# PWR_N3V0.net
KiCad netlist of a schematic drawn in Altium Designer
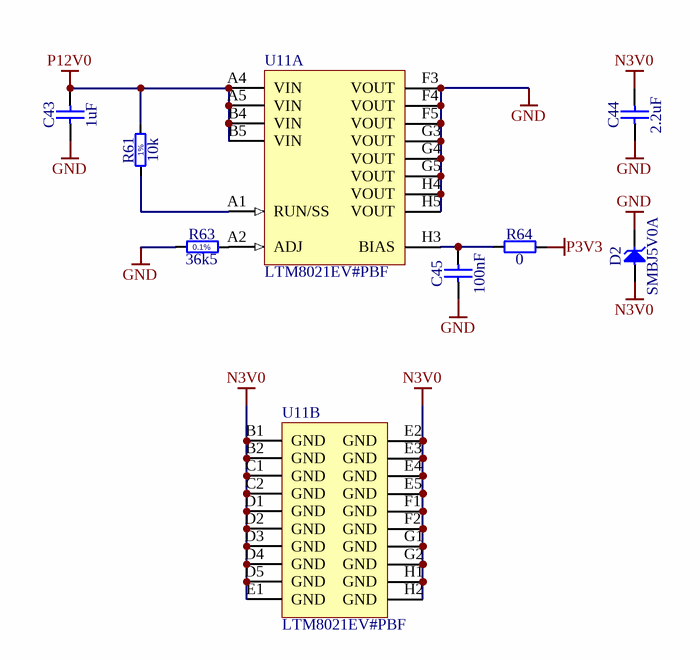
[diagram p0: PWR_N3V0.SchDoc]

(export (version "E")
  (design (tool "Eeschema 10.0.6"))
  (components
    (comp (ref "C43")
      (value "1uF")
      (footprint "CAPC1608X87N")
      (description "Non-polarised capacitor")
      (fields
        (field (name "PART NUMBER") "CC0603_1UF_25V_10%_X7R")
        (field (name "VOLTAGE") "25V")
        (field (name "AUTHOR") "CERN DEM JLC")
      )
      (libsource (lib "Capacitors") (part "Capacitor - non polarized"))
    )
    (comp (ref "C44")
      (value "2.2uF")
      (footprint "CAPC1608X87N")
      (description "Non-polarised capacitor")
      (fields
        (field (name "PART NUMBER") "CC0603_2.2UF_16V_10%_X5R")
        (field (name "VOLTAGE") "16V")
        (field (name "AUTHOR") "CERN DEM JLC")
      )
      (libsource (lib "Capacitors") (part "Capacitor - non polarized"))
    )
    (comp (ref "C45")
      (value "100nF")
      (footprint "CAPC1005X55N")
      (description "Non-polarised capacitor")
      (fields
        (field (name "PART NUMBER") "CC0402_100NF_16V_10%_X5R")
        (field (name "VOLTAGE") "16V")
        (field (name "AUTHOR") "CERN DEM JLC")
      )
      (libsource (lib "Capacitors") (part "Capacitor - non polarized"))
    )
    (comp (ref "D2")
      (value "SMBJ5V0A")
      (footprint "DIOM5336X265N")
      (description "Zener Diode")
      (fields
        (field (name "VOLTAGE") "5V")
        (field (name "POWER") "600W")
        (field (name "AUTHOR") "CERN DEM JLC")
      )
      (libsource (lib "ICs And Semiconductors") (part "Diode Zener"))
    )
    (comp (ref "R61")
      (value "10k")
      (footprint "RESC1005X40N")
      (description "Resistor - 1%")
      (fields
        (field (name "PART NUMBER") "R0402_10K_1%_0.0625W_100PPM")
        (field (name "MANUFACTURER") "GENERIC")
        (field (name "AUTHOR") "CERN DEM JLC")
      )
      (libsource (lib "Resistors") (part "Resistor - 1%"))
    )
    (comp (ref "R63")
      (value "36k5")
      (footprint "RESC1608X55N")
      (description "Resistor - 0.1%")
      (fields
        (field (name "PART NUMBER") "R0603_36K5_0.1%_0.063W_10PPM")
        (field (name "POWER") "0.063W")
        (field (name "AUTHOR") "CERN DEM JLC")
      )
      (libsource (lib "Resistors") (part "Resistor - 0.1%"))
    )
    (comp (ref "R64")
      (value "0")
      (footprint "RESC1005X40N")
      (description "Resistor")
      (fields
        (field (name "PART NUMBER") "R0402_0R_JUMPER")
        (field (name "MANUFACTURER") "GENERIC")
        (field (name "AUTHOR") "CERN DEM JLC")
      )
      (libsource (lib "Resistors") (part "Resistor"))
    )
    (comp (ref "U11")
      (value "LTM8021EV#PBF")
      (footprint "LT-LGA-35-11250X6250X2820_V")
      (description "36 VIN, 500 mA Step-Down DC/DC uModule, 35-pin LGA, -40 to 125 degC, Pb-Free, Tray")
      (fields (field (name "MANUFACTURER") "Linear Technology"))
      (libsource (lib "Altium Content Vault") (part "LT-LTM8021-LGA-35"))
    )
  )
  (nets
    (net (code "1") (name "GND") (class "Default")
      (node (ref "C43") (pin "1") (pinfunction "1_1") (pintype "passive"))
      (node (ref "C44") (pin "1") (pinfunction "1_1") (pintype "passive"))
      (node (ref "C45") (pin "1") (pinfunction "1_1") (pintype "passive"))
      (node (ref "D2") (pin "1") (pinfunction "C_1") (pintype "passive"))
      (node (ref "R63") (pin "1") (pinfunction "1_1") (pintype "passive"))
      (node (ref "U11") (pin "F3") (pinfunction "VOUT_F3") (pintype "power_in"))
      (node (ref "U11") (pin "F4") (pinfunction "VOUT_F4") (pintype "power_in"))
      (node (ref "U11") (pin "F5") (pinfunction "VOUT_F5") (pintype "power_in"))
      (node (ref "U11") (pin "G3") (pinfunction "VOUT_G3") (pintype "power_in"))
      (node (ref "U11") (pin "G4") (pinfunction "VOUT_G4") (pintype "power_in"))
      (node (ref "U11") (pin "G5") (pinfunction "VOUT_G5") (pintype "power_in"))
      (node (ref "U11") (pin "H4") (pinfunction "VOUT_H4") (pintype "power_in"))
      (node (ref "U11") (pin "H5") (pinfunction "VOUT_H5") (pintype "power_in"))
    )
    (net (code "2") (name "N3V0") (class "Default")
      (node (ref "C44") (pin "2") (pinfunction "2_2") (pintype "passive"))
      (node (ref "D2") (pin "2") (pinfunction "A_2") (pintype "passive"))
      (node (ref "U11") (pin "B1") (pinfunction "GND_B1") (pintype "power_in"))
      (node (ref "U11") (pin "B2") (pinfunction "GND_B2") (pintype "power_in"))
      (node (ref "U11") (pin "C1") (pinfunction "GND_C1") (pintype "power_in"))
      (node (ref "U11") (pin "C2") (pinfunction "GND_C2") (pintype "power_in"))
      (node (ref "U11") (pin "D1") (pinfunction "GND_D1") (pintype "power_in"))
      (node (ref "U11") (pin "D2") (pinfunction "GND_D2") (pintype "power_in"))
      (node (ref "U11") (pin "D3") (pinfunction "GND_D3") (pintype "power_in"))
      (node (ref "U11") (pin "D4") (pinfunction "GND_D4") (pintype "power_in"))
      (node (ref "U11") (pin "D5") (pinfunction "GND_D5") (pintype "power_in"))
      (node (ref "U11") (pin "E1") (pinfunction "GND_E1") (pintype "power_in"))
      (node (ref "U11") (pin "E2") (pinfunction "GND_E2") (pintype "power_in"))
      (node (ref "U11") (pin "E3") (pinfunction "GND_E3") (pintype "power_in"))
      (node (ref "U11") (pin "E4") (pinfunction "GND_E4") (pintype "power_in"))
      (node (ref "U11") (pin "E5") (pinfunction "GND_E5") (pintype "power_in"))
      (node (ref "U11") (pin "F1") (pinfunction "GND_F1") (pintype "power_in"))
      (node (ref "U11") (pin "F2") (pinfunction "GND_F2") (pintype "power_in"))
      (node (ref "U11") (pin "G1") (pinfunction "GND_G1") (pintype "power_in"))
      (node (ref "U11") (pin "G2") (pinfunction "GND_G2") (pintype "power_in"))
      (node (ref "U11") (pin "H1") (pinfunction "GND_H1") (pintype "power_in"))
      (node (ref "U11") (pin "H2") (pinfunction "GND_H2") (pintype "power_in"))
    )
    (net (code "3") (name "Net-(U11A-ADJ)") (class "Default")
      (node (ref "R63") (pin "2") (pinfunction "2_2") (pintype "passive"))
      (node (ref "U11") (pin "A2") (pinfunction "ADJ_A2") (pintype "input"))
    )
    (net (code "4") (name "Net-(U11A-BIAS)") (class "Default")
      (node (ref "C45") (pin "2") (pinfunction "2_2") (pintype "passive"))
      (node (ref "R64") (pin "1") (pinfunction "1_1") (pintype "passive"))
      (node (ref "U11") (pin "H3") (pinfunction "BIAS_H3") (pintype "power_in"))
    )
    (net (code "5") (name "Net-(U11A-RUN{slash}SS)") (class "Default")
      (node (ref "R61") (pin "1") (pinfunction "1_1") (pintype "passive"))
      (node (ref "U11") (pin "A1") (pinfunction "RUN/SS_A1") (pintype "input"))
    )
    (net (code "6") (name "P3V3") (class "Default")
      (node (ref "R64") (pin "2") (pinfunction "2_2") (pintype "passive"))
    )
    (net (code "7") (name "P12V0") (class "Default")
      (node (ref "C43") (pin "2") (pinfunction "2_2") (pintype "passive"))
      (node (ref "R61") (pin "2") (pinfunction "2_2") (pintype "passive"))
      (node (ref "U11") (pin "A4") (pinfunction "VIN_A4") (pintype "power_in"))
      (node (ref "U11") (pin "A5") (pinfunction "VIN_A5") (pintype "power_in"))
      (node (ref "U11") (pin "B4") (pinfunction "VIN_B4") (pintype "power_in"))
      (node (ref "U11") (pin "B5") (pinfunction "VIN_B5") (pintype "power_in"))
    )
  )
)
